# RNS.net
KiCad netlist of a schematic drawn in EAGLE
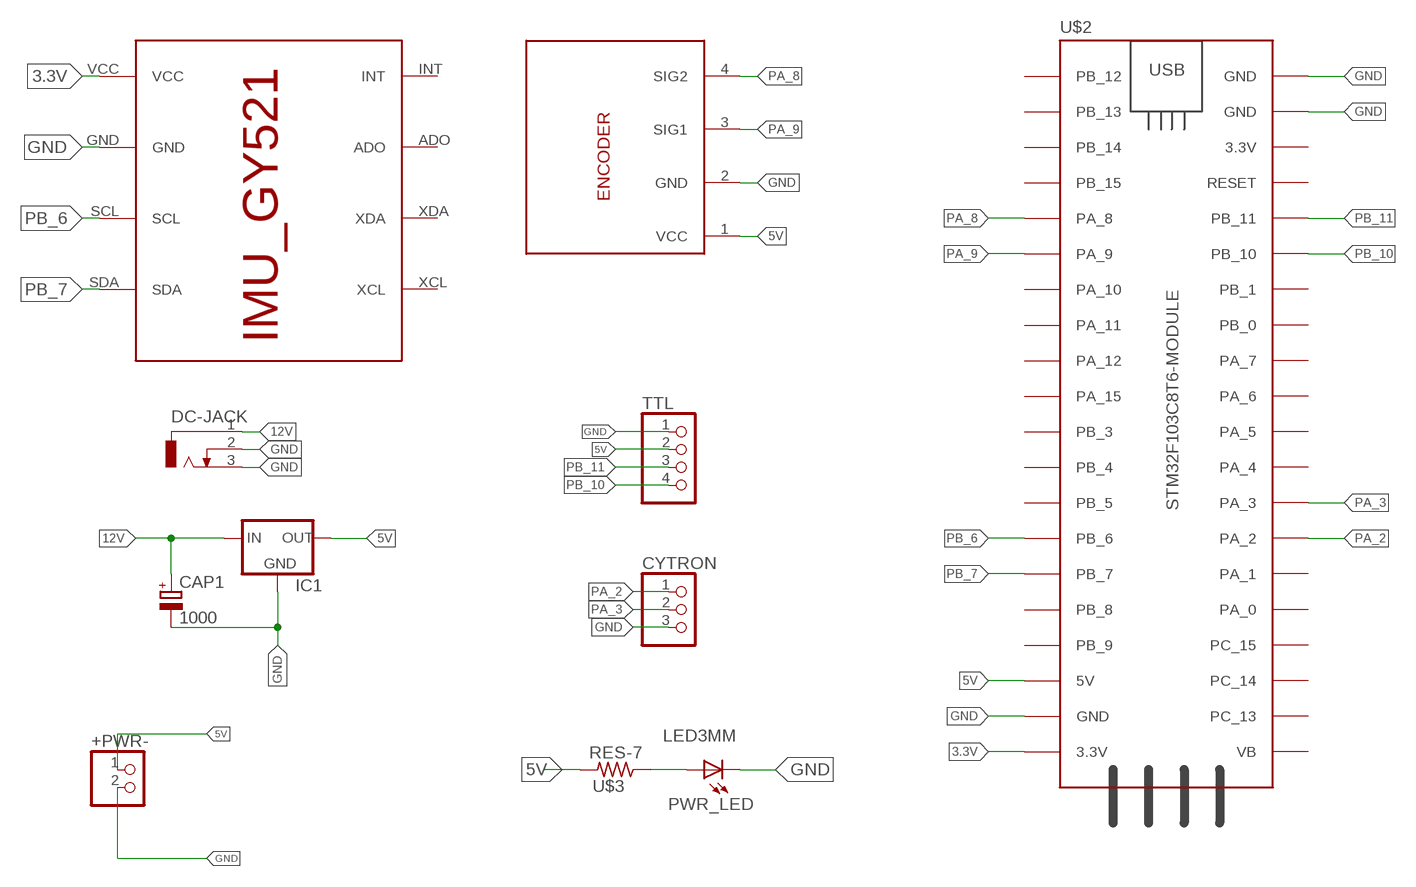
[diagram p0: schematic, sheet 1]

(export (version "E")
  (design (tool "Eeschema 10.0.6"))
  (components
    (comp (ref "+PWR-")
      (value "PINHD-1X2")
      (footprint "eagle-import:1X02")
      (libsource (lib "eagle-import") (part "PINHD-1X2"))
    )
    (comp (ref "CAP1")
      (value "1000")
      (footprint "eagle-import:E3,5-8")
      (libsource (lib "eagle-import") (part "CAP_POL"))
    )
    (comp (ref "CYTRON")
      (value "PINHD-1X3")
      (footprint "eagle-import:1X03")
      (libsource (lib "eagle-import") (part "PINHD-1X3"))
    )
    (comp (ref "DC-JACK")
      (value "CON_JACK")
      (footprint "eagle-import:DCJ0303")
      (libsource (lib "eagle-import") (part "CON_JACK"))
    )
    (comp (ref "IC1")
      (value "78XXL")
      (footprint "eagle-import:78XXL")
      (libsource (lib "eagle-import") (part "78XXL"))
    )
    (comp (ref "PWR_LED")
      (value "LED3MM")
      (footprint "eagle-import:LED3MM")
      (libsource (lib "eagle-import") (part "LED3MM"))
    )
    (comp (ref "TTL")
      (value "PINHD-1X4")
      (footprint "eagle-import:1X04")
      (libsource (lib "eagle-import") (part "PINHD-1X4"))
    )
    (comp (ref "U$1")
      (value "ENCODER")
      (footprint "eagle-import:1X04_DATA")
      (libsource (lib "eagle-import") (part "ENCODER"))
    )
    (comp (ref "U$2")
      (value "STM32F103C8T6-MODULE")
      (footprint "eagle-import:STM32F103C8T6-MODULE")
      (libsource (lib "eagle-import") (part "STM32F103C8T6-MODULE"))
    )
    (comp (ref "U$3")
      (value "RES-7")
      (footprint "eagle-import:0204_7")
      (libsource (lib "eagle-import") (part "RES-7"))
    )
    (comp (ref "U$4")
      (value "IMU_ROBOCON_GY521")
      (footprint "eagle-import:IMU_GY521")
      (libsource (lib "eagle-import") (part "IMU_ROBOCON_GY521"))
    )
  )
  (nets
    (net (code "1") (name "3.3V") (class "Default")
      (node (ref "U$2") (pin "3.3V_1") (pinfunction "3.3V_3.3V_1") (pintype "bidirectional"))
      (node (ref "U$4") (pin "VCC") (pinfunction "VCC_VCC") (pintype "bidirectional"))
    )
    (net (code "2") (name "5V") (class "Default")
      (node (ref "+PWR-") (pin "1") (pinfunction "1_1") (pintype "passive"))
      (node (ref "IC1") (pin "OUT") (pinfunction "OUT_OUT") (pintype "passive"))
      (node (ref "TTL") (pin "2") (pinfunction "2_2") (pintype "passive"))
      (node (ref "U$1") (pin "1") (pinfunction "VCC_1") (pintype "bidirectional"))
      (node (ref "U$2") (pin "5V") (pinfunction "5V_5V") (pintype "bidirectional"))
      (node (ref "U$3") (pin "2") (pinfunction "2_2") (pintype "passive"))
    )
    (net (code "3") (name "12V") (class "Default")
      (node (ref "CAP1") (pin "+") (pinfunction "+_+") (pintype "passive"))
      (node (ref "DC-JACK") (pin "1") (pinfunction "1_1") (pintype "passive"))
      (node (ref "IC1") (pin "IN") (pinfunction "IN_IN") (pintype "input"))
    )
    (net (code "4") (name "GND") (class "Default")
      (node (ref "+PWR-") (pin "2") (pinfunction "2_2") (pintype "passive"))
      (node (ref "CAP1") (pin "-") (pinfunction "-_-") (pintype "passive"))
      (node (ref "CYTRON") (pin "3") (pinfunction "3_3") (pintype "passive"))
      (node (ref "DC-JACK") (pin "2") (pinfunction "2_2") (pintype "passive"))
      (node (ref "DC-JACK") (pin "3") (pinfunction "3_3") (pintype "passive"))
      (node (ref "IC1") (pin "GND") (pinfunction "GND_GND") (pintype "input"))
      (node (ref "PWR_LED") (pin "K") (pinfunction "C_K") (pintype "passive"))
      (node (ref "TTL") (pin "1") (pinfunction "1_1") (pintype "passive"))
      (node (ref "U$1") (pin "2") (pinfunction "GND_2") (pintype "bidirectional"))
      (node (ref "U$2") (pin "GND_1") (pinfunction "GND_GND_1") (pintype "bidirectional"))
      (node (ref "U$2") (pin "GND_2") (pinfunction "GND_GND_2") (pintype "bidirectional"))
      (node (ref "U$2") (pin "GND_3") (pinfunction "GND_GND_3") (pintype "power_in"))
      (node (ref "U$4") (pin "GND") (pinfunction "GND_GND") (pintype "bidirectional"))
    )
    (net (code "5") (name "Net-(PWR_LED-PadA)") (class "Default")
      (node (ref "PWR_LED") (pin "A") (pinfunction "A_A") (pintype "passive"))
      (node (ref "U$3") (pin "1") (pinfunction "1_1") (pintype "passive"))
    )
    (net (code "6") (name "PA_2") (class "Default")
      (node (ref "CYTRON") (pin "1") (pinfunction "1_1") (pintype "passive"))
      (node (ref "U$2") (pin "PA_2") (pinfunction "PA_2_PA_2") (pintype "bidirectional"))
    )
    (net (code "7") (name "PA_3") (class "Default")
      (node (ref "CYTRON") (pin "2") (pinfunction "2_2") (pintype "passive"))
      (node (ref "U$2") (pin "PA_3") (pinfunction "PA_3_PA_3") (pintype "bidirectional"))
    )
    (net (code "8") (name "PA_8") (class "Default")
      (node (ref "U$1") (pin "4") (pinfunction "SIG2_4") (pintype "bidirectional"))
      (node (ref "U$2") (pin "PA_8") (pinfunction "PA_8_PA_8") (pintype "bidirectional"))
    )
    (net (code "9") (name "PA_9") (class "Default")
      (node (ref "U$1") (pin "3") (pinfunction "SIG1_3") (pintype "bidirectional"))
      (node (ref "U$2") (pin "PA_9") (pinfunction "PA_9_PA_9") (pintype "bidirectional"))
    )
    (net (code "10") (name "PB_6") (class "Default")
      (node (ref "U$2") (pin "PB_6") (pinfunction "PB_6_PB_6") (pintype "bidirectional"))
      (node (ref "U$4") (pin "SCL") (pinfunction "SCL_SCL") (pintype "bidirectional"))
    )
    (net (code "11") (name "PB_7") (class "Default")
      (node (ref "U$2") (pin "PB_7") (pinfunction "PB_7_PB_7") (pintype "bidirectional"))
      (node (ref "U$4") (pin "SDA") (pinfunction "SDA_SDA") (pintype "bidirectional"))
    )
    (net (code "12") (name "PB_10") (class "Default")
      (node (ref "TTL") (pin "4") (pinfunction "4_4") (pintype "passive"))
      (node (ref "U$2") (pin "PB_10") (pinfunction "PB_10_PB_10") (pintype "bidirectional"))
    )
    (net (code "13") (name "PB_11") (class "Default")
      (node (ref "TTL") (pin "3") (pinfunction "3_3") (pintype "passive"))
      (node (ref "U$2") (pin "PB_11") (pinfunction "PB_11_PB_11") (pintype "bidirectional"))
    )
    (net (code "14") (name "unconnected-(U$2-3.3V-Pad3.3V_2)") (class "Default")
      (node (ref "U$2") (pin "3.3V_2") (pinfunction "3.3V_3.3V_2") (pintype "bidirectional"))
    )
    (net (code "15") (name "unconnected-(U$2-PadPA_0)") (class "Default")
      (node (ref "U$2") (pin "PA_0") (pinfunction "PA_0_PA_0") (pintype "bidirectional"))
    )
    (net (code "16") (name "unconnected-(U$2-PadPA_1)") (class "Default")
      (node (ref "U$2") (pin "PA_1") (pinfunction "PA_1_PA_1") (pintype "bidirectional"))
    )
    (net (code "17") (name "unconnected-(U$2-PadPA_4)") (class "Default")
      (node (ref "U$2") (pin "PA_4") (pinfunction "PA_4_PA_4") (pintype "bidirectional"))
    )
    (net (code "18") (name "unconnected-(U$2-PadPA_5)") (class "Default")
      (node (ref "U$2") (pin "PA_5") (pinfunction "PA_5_PA_5") (pintype "bidirectional"))
    )
    (net (code "19") (name "unconnected-(U$2-PadPA_6)") (class "Default")
      (node (ref "U$2") (pin "PA_6") (pinfunction "PA_6_PA_6") (pintype "bidirectional"))
    )
    (net (code "20") (name "unconnected-(U$2-PadPA_7)") (class "Default")
      (node (ref "U$2") (pin "PA_7") (pinfunction "PA_7_PA_7") (pintype "bidirectional"))
    )
    (net (code "21") (name "unconnected-(U$2-PadPA_10)") (class "Default")
      (node (ref "U$2") (pin "PA_10") (pinfunction "PA_10_PA_10") (pintype "bidirectional"))
    )
    (net (code "22") (name "unconnected-(U$2-PadPA_11)") (class "Default")
      (node (ref "U$2") (pin "PA_11") (pinfunction "PA_11_PA_11") (pintype "bidirectional"))
    )
    (net (code "23") (name "unconnected-(U$2-PadPA_12)") (class "Default")
      (node (ref "U$2") (pin "PA_12") (pinfunction "PA_12_PA_12") (pintype "bidirectional"))
    )
    (net (code "24") (name "unconnected-(U$2-PadPA_15)") (class "Default")
      (node (ref "U$2") (pin "PA_15") (pinfunction "PA_15_PA_15") (pintype "bidirectional"))
    )
    (net (code "25") (name "unconnected-(U$2-PadPB_0)") (class "Default")
      (node (ref "U$2") (pin "PB_0") (pinfunction "PB_0_PB_0") (pintype "bidirectional"))
    )
    (net (code "26") (name "unconnected-(U$2-PadPB_1)") (class "Default")
      (node (ref "U$2") (pin "PB_1") (pinfunction "PB_1_PB_1") (pintype "bidirectional"))
    )
    (net (code "27") (name "unconnected-(U$2-PadPB_3)") (class "Default")
      (node (ref "U$2") (pin "PB_3") (pinfunction "PB_3_PB_3") (pintype "bidirectional"))
    )
    (net (code "28") (name "unconnected-(U$2-PadPB_4)") (class "Default")
      (node (ref "U$2") (pin "PB_4") (pinfunction "PB_4_PB_4") (pintype "bidirectional"))
    )
    (net (code "29") (name "unconnected-(U$2-PadPB_5)") (class "Default")
      (node (ref "U$2") (pin "PB_5") (pinfunction "PB_5_PB_5") (pintype "bidirectional"))
    )
    (net (code "30") (name "unconnected-(U$2-PadPB_8)") (class "Default")
      (node (ref "U$2") (pin "PB_8") (pinfunction "PB_8_PB_8") (pintype "bidirectional"))
    )
    (net (code "31") (name "unconnected-(U$2-PadPB_9)") (class "Default")
      (node (ref "U$2") (pin "PB_9") (pinfunction "PB_9_PB_9") (pintype "bidirectional"))
    )
    (net (code "32") (name "unconnected-(U$2-PadPB_12)") (class "Default")
      (node (ref "U$2") (pin "PB_12") (pinfunction "PB_12_PB_12") (pintype "bidirectional"))
    )
    (net (code "33") (name "unconnected-(U$2-PadPB_13)") (class "Default")
      (node (ref "U$2") (pin "PB_13") (pinfunction "PB_13_PB_13") (pintype "bidirectional"))
    )
    (net (code "34") (name "unconnected-(U$2-PadPB_14)") (class "Default")
      (node (ref "U$2") (pin "PB_14") (pinfunction "PB_14_PB_14") (pintype "bidirectional"))
    )
    (net (code "35") (name "unconnected-(U$2-PadPB_15)") (class "Default")
      (node (ref "U$2") (pin "PB_15") (pinfunction "PB_15_PB_15") (pintype "bidirectional"))
    )
    (net (code "36") (name "unconnected-(U$2-PadPC_13)") (class "Default")
      (node (ref "U$2") (pin "PC_13") (pinfunction "PC_13_PC_13") (pintype "bidirectional"))
    )
    (net (code "37") (name "unconnected-(U$2-PadPC_14)") (class "Default")
      (node (ref "U$2") (pin "PC_14") (pinfunction "PC_14_PC_14") (pintype "bidirectional"))
    )
    (net (code "38") (name "unconnected-(U$2-PadPC_15)") (class "Default")
      (node (ref "U$2") (pin "PC_15") (pinfunction "PC_15_PC_15") (pintype "bidirectional"))
    )
    (net (code "39") (name "unconnected-(U$2-PadRESET)") (class "Default")
      (node (ref "U$2") (pin "RESET") (pinfunction "RESET_RESET") (pintype "bidirectional"))
    )
    (net (code "40") (name "unconnected-(U$2-PadVB)") (class "Default")
      (node (ref "U$2") (pin "VB") (pinfunction "VB_VB") (pintype "bidirectional"))
    )
    (net (code "41") (name "unconnected-(U$4-PadADO)") (class "Default")
      (node (ref "U$4") (pin "ADO") (pinfunction "ADO_ADO") (pintype "bidirectional"))
    )
    (net (code "42") (name "unconnected-(U$4-PadINT)") (class "Default")
      (node (ref "U$4") (pin "INT") (pinfunction "INT_INT") (pintype "bidirectional"))
    )
    (net (code "43") (name "unconnected-(U$4-PadXCL)") (class "Default")
      (node (ref "U$4") (pin "XCL") (pinfunction "XCL_XCL") (pintype "bidirectional"))
    )
    (net (code "44") (name "unconnected-(U$4-PadXDA)") (class "Default")
      (node (ref "U$4") (pin "XDA") (pinfunction "XDA_XDA") (pintype "bidirectional"))
    )
  )
)
